# jlpcb-184.net
KiCad netlist of a schematic drawn in EAGLE
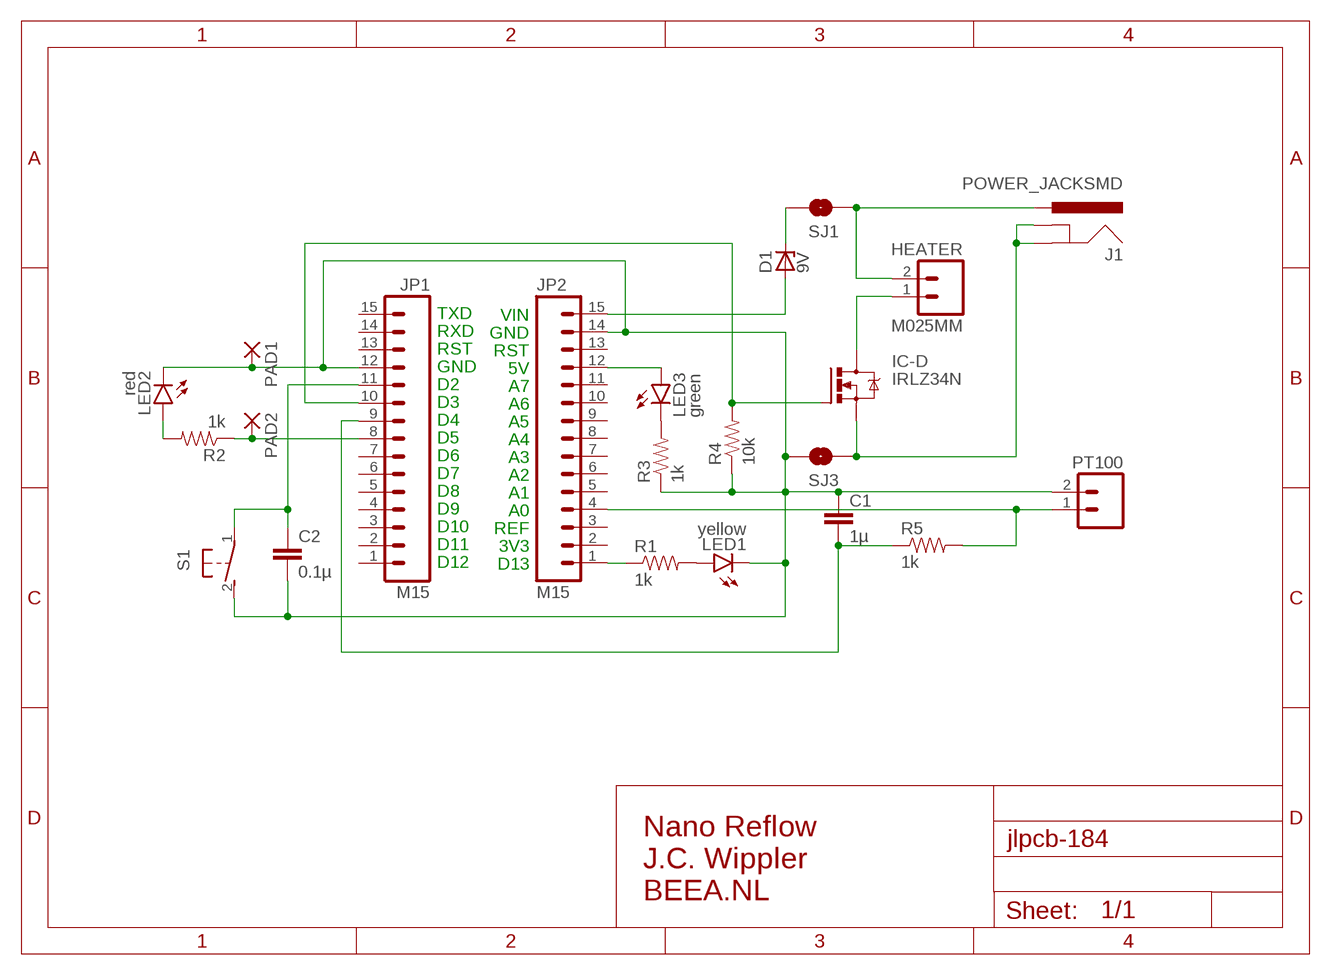
[diagram p0: schematic, sheet 1]

(export (version "E")
  (design (tool "Eeschema 10.0.6"))
  (components
    (comp (ref "C1")
      (value "1µ")
      (footprint "eagle-import:CAP-PTH-5MM")
      (libsource (lib "eagle-import") (part "CAPPTH1"))
    )
    (comp (ref "C2")
      (value "0.1µ")
      (footprint "eagle-import:CAP-PTH-SMALL")
      (libsource (lib "eagle-import") (part "CAPPTH"))
    )
    (comp (ref "D1")
      (value "9V")
      (footprint "eagle-import:DO35Z10")
      (libsource (lib "eagle-import") (part "ZENER-DIODEDO35Z10"))
    )
    (comp (ref "HEATER")
      (value "M025MM")
      (footprint "eagle-import:SCREWTERMINAL-5MM-2")
      (libsource (lib "eagle-import") (part "M025MM"))
    )
    (comp (ref "IC-D")
      (value "IRLZ34N")
      (footprint "eagle-import:TO220BV")
      (libsource (lib "eagle-import") (part "IRF540"))
    )
    (comp (ref "J1")
      (value "POWER_JACKSMD")
      (footprint "eagle-import:POWER_JACK_SMD")
      (libsource (lib "eagle-import") (part "POWER_JACKSMD"))
    )
    (comp (ref "JP1")
      (value "M15")
      (footprint "eagle-import:1X15")
      (libsource (lib "eagle-import") (part "M15"))
    )
    (comp (ref "JP2")
      (value "M15")
      (footprint "eagle-import:1X15")
      (libsource (lib "eagle-import") (part "M15"))
    )
    (comp (ref "LED1")
      (value "yellow")
      (footprint "eagle-import:LED3MM")
      (libsource (lib "eagle-import") (part "LED3MM"))
    )
    (comp (ref "LED2")
      (value "red")
      (footprint "eagle-import:LED3MM")
      (libsource (lib "eagle-import") (part "LED3MM"))
    )
    (comp (ref "LED3")
      (value "green")
      (footprint "eagle-import:LED3MM")
      (libsource (lib "eagle-import") (part "LED3MM"))
    )
    (comp (ref "PAD1")
      (value "1,6/0,8")
      (footprint "eagle-import:1,6_0,8")
      (libsource (lib "eagle-import") (part "1,6/0,8"))
    )
    (comp (ref "PAD2")
      (value "1,6/0,8")
      (footprint "eagle-import:1,6_0,8")
      (libsource (lib "eagle-import") (part "1,6/0,8"))
    )
    (comp (ref "PT100")
      (value "M023.5MM")
      (footprint "eagle-import:SCREWTERMINAL-3.5MM-2")
      (libsource (lib "eagle-import") (part "M023.5MM"))
    )
    (comp (ref "R1")
      (value "1k")
      (footprint "eagle-import:AXIAL-0.3")
      (libsource (lib "eagle-import") (part "RESISTORAXIAL-0.3"))
    )
    (comp (ref "R2")
      (value "1k")
      (footprint "eagle-import:AXIAL-0.3")
      (libsource (lib "eagle-import") (part "RESISTORAXIAL-0.3"))
    )
    (comp (ref "R3")
      (value "1k")
      (footprint "eagle-import:AXIAL-0.3")
      (libsource (lib "eagle-import") (part "RESISTORAXIAL-0.3"))
    )
    (comp (ref "R4")
      (value "10k")
      (footprint "eagle-import:AXIAL-0.3")
      (libsource (lib "eagle-import") (part "RESISTORAXIAL-0.3"))
    )
    (comp (ref "R5")
      (value "1k")
      (footprint "eagle-import:AXIAL-0.3")
      (libsource (lib "eagle-import") (part "RESISTORAXIAL-0.3"))
    )
    (comp (ref "S1")
      (value "31-XX")
      (footprint "eagle-import:B3F-31XX")
      (libsource (lib "eagle-import") (part "31-XX"))
    )
    (comp (ref "SJ1")
      (value "SOLDERJUMPERTRACE")
      (footprint "eagle-import:SJ_2S-TRACE")
      (libsource (lib "eagle-import") (part "SOLDERJUMPERTRACE"))
    )
    (comp (ref "SJ3")
      (value "SOLDERJUMPERTRACE")
      (footprint "eagle-import:SJ_2S-TRACE")
      (libsource (lib "eagle-import") (part "SOLDERJUMPERTRACE"))
    )
  )
  (nets
    (net (code "1") (name "Net-(D1-PadA)") (class "Default")
      (node (ref "D1") (pin "A") (pinfunction "A_A") (pintype "passive"))
      (node (ref "JP2") (pin "15") (pinfunction "15_15") (pintype "passive"))
    )
    (net (code "2") (name "Net-(D1-PadC)") (class "Default")
      (node (ref "D1") (pin "C") (pinfunction "C_C") (pintype "passive"))
      (node (ref "SJ1") (pin "2") (pinfunction "2_2") (pintype "passive"))
    )
    (net (code "3") (name "Net-(HEATER-Pad1)") (class "Default")
      (node (ref "HEATER") (pin "1") (pinfunction "1_1") (pintype "passive"))
      (node (ref "IC-D") (pin "D") (pinfunction "D_D") (pintype "passive"))
    )
    (net (code "4") (name "Net-(J1-GND)") (class "Default")
      (node (ref "IC-D") (pin "S") (pinfunction "S_S") (pintype "passive"))
      (node (ref "J1") (pin "GND") (pinfunction "GNDBREAK_GND") (pintype "bidirectional"))
      (node (ref "J1") (pin "P$4") (pinfunction "GND_P$4") (pintype "bidirectional"))
      (node (ref "SJ3") (pin "1") (pinfunction "1_1") (pintype "passive"))
    )
    (net (code "5") (name "Net-(J1-PWR)") (class "Default")
      (node (ref "HEATER") (pin "2") (pinfunction "2_2") (pintype "passive"))
      (node (ref "J1") (pin "VIN0") (pinfunction "PWR_VIN0") (pintype "bidirectional"))
      (node (ref "SJ1") (pin "1") (pinfunction "1_1") (pintype "passive"))
    )
    (net (code "6") (name "Net-(JP2-Pad12)") (class "Default")
      (node (ref "JP2") (pin "12") (pinfunction "12_12") (pintype "passive"))
      (node (ref "LED3") (pin "A") (pinfunction "A_A") (pintype "passive"))
    )
    (net (code "7") (name "Net-(LED1-C)") (class "Default")
      (node (ref "C1") (pin "1") (pinfunction "1_1") (pintype "passive"))
      (node (ref "C2") (pin "2") (pinfunction "2_2") (pintype "passive"))
      (node (ref "JP1") (pin "12") (pinfunction "12_12") (pintype "passive"))
      (node (ref "JP2") (pin "14") (pinfunction "14_14") (pintype "passive"))
      (node (ref "LED1") (pin "K") (pinfunction "C_K") (pintype "passive"))
      (node (ref "LED2") (pin "K") (pinfunction "C_K") (pintype "passive"))
      (node (ref "PAD1") (pin "1") (pinfunction "P_1") (pintype "passive"))
      (node (ref "PT100") (pin "2") (pinfunction "2_2") (pintype "passive"))
      (node (ref "R3") (pin "P$1") (pinfunction "1_P$1") (pintype "passive"))
      (node (ref "R4") (pin "P$1") (pinfunction "1_P$1") (pintype "passive"))
      (node (ref "S1") (pin "2") (pinfunction "S_2") (pintype "passive"))
      (node (ref "SJ3") (pin "2") (pinfunction "2_2") (pintype "passive"))
    )
    (net (code "8") (name "Net-(LED3-C)") (class "Default")
      (node (ref "LED3") (pin "K") (pinfunction "C_K") (pintype "passive"))
      (node (ref "R3") (pin "P$2") (pinfunction "2_P$2") (pintype "passive"))
    )
    (net (code "9") (name "Net-(PAD2-P)") (class "Default")
      (node (ref "JP1") (pin "8") (pinfunction "8_8") (pintype "passive"))
      (node (ref "PAD2") (pin "1") (pinfunction "P_1") (pintype "passive"))
      (node (ref "R2") (pin "P$1") (pinfunction "1_P$1") (pintype "passive"))
    )
    (net (code "10") (name "Net-(R1-1)") (class "Default")
      (node (ref "JP2") (pin "1") (pinfunction "1_1") (pintype "passive"))
      (node (ref "R1") (pin "P$1") (pinfunction "1_P$1") (pintype "passive"))
    )
    (net (code "11") (name "Net-(R1-2)") (class "Default")
      (node (ref "LED1") (pin "A") (pinfunction "A_A") (pintype "passive"))
      (node (ref "R1") (pin "P$2") (pinfunction "2_P$2") (pintype "passive"))
    )
    (net (code "12") (name "Net-(R2-2)") (class "Default")
      (node (ref "LED2") (pin "A") (pinfunction "A_A") (pintype "passive"))
      (node (ref "R2") (pin "P$2") (pinfunction "2_P$2") (pintype "passive"))
    )
    (net (code "13") (name "Net-(R4-2)") (class "Default")
      (node (ref "IC-D") (pin "G") (pinfunction "G_G") (pintype "passive"))
      (node (ref "JP1") (pin "10") (pinfunction "10_10") (pintype "passive"))
      (node (ref "R4") (pin "P$2") (pinfunction "2_P$2") (pintype "passive"))
    )
    (net (code "14") (name "Net-(R5-1)") (class "Default")
      (node (ref "C1") (pin "2") (pinfunction "2_2") (pintype "passive"))
      (node (ref "JP1") (pin "9") (pinfunction "9_9") (pintype "passive"))
      (node (ref "R5") (pin "P$1") (pinfunction "1_P$1") (pintype "passive"))
    )
    (net (code "15") (name "Net-(R5-2)") (class "Default")
      (node (ref "JP2") (pin "4") (pinfunction "4_4") (pintype "passive"))
      (node (ref "PT100") (pin "1") (pinfunction "1_1") (pintype "passive"))
      (node (ref "R5") (pin "P$2") (pinfunction "2_P$2") (pintype "passive"))
    )
    (net (code "16") (name "Net-(S1-P)") (class "Default")
      (node (ref "C2") (pin "1") (pinfunction "1_1") (pintype "passive"))
      (node (ref "JP1") (pin "11") (pinfunction "11_11") (pintype "passive"))
      (node (ref "S1") (pin "1") (pinfunction "P_1") (pintype "passive"))
    )
    (net (code "17") (name "unconnected-(JP1-Pad1)") (class "Default")
      (node (ref "JP1") (pin "1") (pinfunction "1_1") (pintype "passive"))
    )
    (net (code "18") (name "unconnected-(JP1-Pad2)") (class "Default")
      (node (ref "JP1") (pin "2") (pinfunction "2_2") (pintype "passive"))
    )
    (net (code "19") (name "unconnected-(JP1-Pad3)") (class "Default")
      (node (ref "JP1") (pin "3") (pinfunction "3_3") (pintype "passive"))
    )
    (net (code "20") (name "unconnected-(JP1-Pad4)") (class "Default")
      (node (ref "JP1") (pin "4") (pinfunction "4_4") (pintype "passive"))
    )
    (net (code "21") (name "unconnected-(JP1-Pad5)") (class "Default")
      (node (ref "JP1") (pin "5") (pinfunction "5_5") (pintype "passive"))
    )
    (net (code "22") (name "unconnected-(JP1-Pad6)") (class "Default")
      (node (ref "JP1") (pin "6") (pinfunction "6_6") (pintype "passive"))
    )
    (net (code "23") (name "unconnected-(JP1-Pad7)") (class "Default")
      (node (ref "JP1") (pin "7") (pinfunction "7_7") (pintype "passive"))
    )
    (net (code "24") (name "unconnected-(JP1-Pad13)") (class "Default")
      (node (ref "JP1") (pin "13") (pinfunction "13_13") (pintype "passive"))
    )
    (net (code "25") (name "unconnected-(JP1-Pad14)") (class "Default")
      (node (ref "JP1") (pin "14") (pinfunction "14_14") (pintype "passive"))
    )
    (net (code "26") (name "unconnected-(JP1-Pad15)") (class "Default")
      (node (ref "JP1") (pin "15") (pinfunction "15_15") (pintype "passive"))
    )
    (net (code "27") (name "unconnected-(JP2-Pad2)") (class "Default")
      (node (ref "JP2") (pin "2") (pinfunction "2_2") (pintype "passive"))
    )
    (net (code "28") (name "unconnected-(JP2-Pad3)") (class "Default")
      (node (ref "JP2") (pin "3") (pinfunction "3_3") (pintype "passive"))
    )
    (net (code "29") (name "unconnected-(JP2-Pad5)") (class "Default")
      (node (ref "JP2") (pin "5") (pinfunction "5_5") (pintype "passive"))
    )
    (net (code "30") (name "unconnected-(JP2-Pad6)") (class "Default")
      (node (ref "JP2") (pin "6") (pinfunction "6_6") (pintype "passive"))
    )
    (net (code "31") (name "unconnected-(JP2-Pad7)") (class "Default")
      (node (ref "JP2") (pin "7") (pinfunction "7_7") (pintype "passive"))
    )
    (net (code "32") (name "unconnected-(JP2-Pad8)") (class "Default")
      (node (ref "JP2") (pin "8") (pinfunction "8_8") (pintype "passive"))
    )
    (net (code "33") (name "unconnected-(JP2-Pad9)") (class "Default")
      (node (ref "JP2") (pin "9") (pinfunction "9_9") (pintype "passive"))
    )
    (net (code "34") (name "unconnected-(JP2-Pad10)") (class "Default")
      (node (ref "JP2") (pin "10") (pinfunction "10_10") (pintype "passive"))
    )
    (net (code "35") (name "unconnected-(JP2-Pad11)") (class "Default")
      (node (ref "JP2") (pin "11") (pinfunction "11_11") (pintype "passive"))
    )
    (net (code "36") (name "unconnected-(JP2-Pad13)") (class "Default")
      (node (ref "JP2") (pin "13") (pinfunction "13_13") (pintype "passive"))
    )
  )
)
